# 4313_Breakout_V1_0.net
KiCad netlist of a schematic drawn in EAGLE
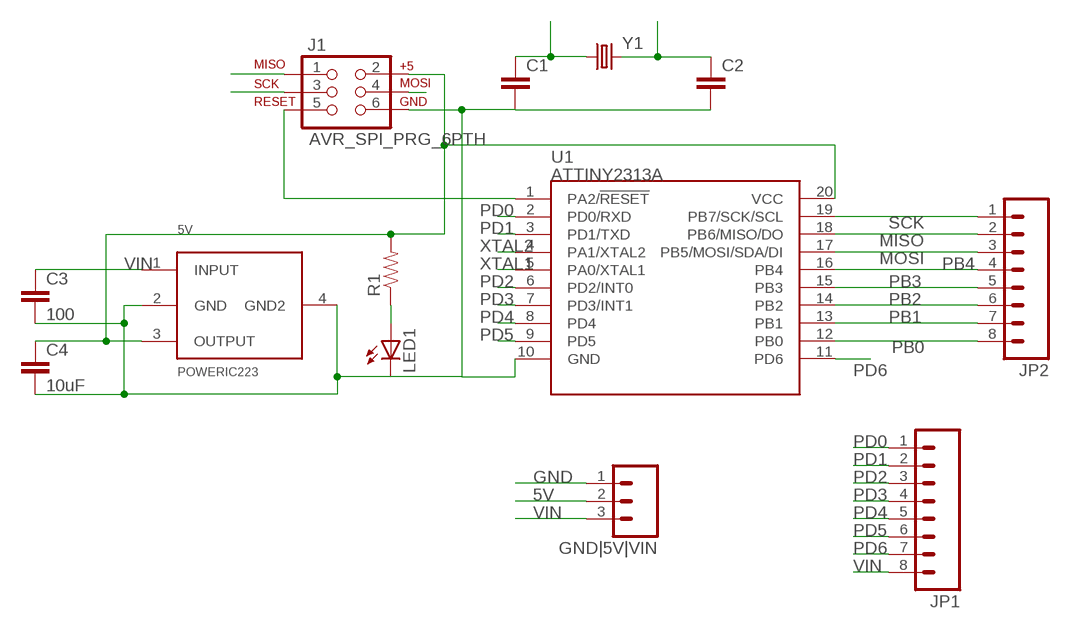
[diagram p0: schematic, sheet 1]

(export (version "E")
  (design (tool "Eeschema 10.0.6"))
  (components
    (comp (ref "5V")
      (value "POWERIC223")
      (footprint "eagle-import:SOT223")
      (libsource (lib "eagle-import") (part "POWERIC223"))
    )
    (comp (ref "C1")
      (value "CAP1206")
      (footprint "eagle-import:1206")
      (libsource (lib "eagle-import") (part "SparkFun-Passives_CAP1206"))
    )
    (comp (ref "C2")
      (value "CAP1206")
      (footprint "eagle-import:1206")
      (libsource (lib "eagle-import") (part "SparkFun-Passives_CAP1206"))
    )
    (comp (ref "C3")
      (value "100")
      (footprint "eagle-import:1210")
      (libsource (lib "eagle-import") (part "CAP1210"))
    )
    (comp (ref "C4")
      (value "10uF")
      (footprint "eagle-import:1210")
      (libsource (lib "eagle-import") (part "CAP1210"))
    )
    (comp (ref "GND|5V|VIN")
      (value "M03PTH")
      (footprint "eagle-import:1X03")
      (libsource (lib "eagle-import") (part "M03PTH"))
    )
    (comp (ref "J1")
      (value "AVR_SPI_PRG_6PTH")
      (footprint "eagle-import:2X3")
      (libsource (lib "eagle-import") (part "AVR_SPI_PRG_6PTH"))
    )
    (comp (ref "JP1")
      (value "M081X08")
      (footprint "eagle-import:1X08")
      (libsource (lib "eagle-import") (part "M081X08"))
    )
    (comp (ref "JP2")
      (value "M081X08")
      (footprint "eagle-import:1X08")
      (libsource (lib "eagle-import") (part "M081X08"))
    )
    (comp (ref "LED1")
      (value "LED1206")
      (footprint "eagle-import:LED-1206")
      (libsource (lib "eagle-import") (part "LED1206"))
    )
    (comp (ref "R1")
      (value "RESISTOR1206")
      (footprint "eagle-import:1206")
      (libsource (lib "eagle-import") (part "RESISTOR1206"))
    )
    (comp (ref "U1")
      (value "ATTINY2313A")
      (footprint "eagle-import:SOP20W")
      (libsource (lib "eagle-import") (part "ATTINY2313A"))
    )
    (comp (ref "Y1")
      (value "CRYSTALHC49US")
      (footprint "eagle-import:HC49US")
      (libsource (lib "eagle-import") (part "CRYSTALHC49US"))
    )
  )
  (nets
    (net (code "1") (name "/5V") (class "Default")
      (node (ref "5V") (pin "3") (pinfunction "OUTPUT_3") (pintype "bidirectional"))
      (node (ref "C4") (pin "1") (pinfunction "1_1") (pintype "passive"))
      (node (ref "GND|5V|VIN") (pin "2") (pinfunction "2_2") (pintype "passive"))
      (node (ref "J1") (pin "2") (pinfunction "2_2") (pintype "passive"))
      (node (ref "R1") (pin "2") (pinfunction "2_2") (pintype "passive"))
      (node (ref "U1") (pin "20") (pinfunction "VCC_20") (pintype "bidirectional"))
    )
    (net (code "2") (name "/GND") (class "Default")
      (node (ref "5V") (pin "2") (pinfunction "GND_2") (pintype "bidirectional"))
      (node (ref "5V") (pin "4") (pinfunction "GND2_4") (pintype "bidirectional"))
      (node (ref "C1") (pin "2") (pinfunction "2_2") (pintype "passive"))
      (node (ref "C2") (pin "2") (pinfunction "2_2") (pintype "passive"))
      (node (ref "C3") (pin "2") (pinfunction "2_2") (pintype "passive"))
      (node (ref "C4") (pin "2") (pinfunction "2_2") (pintype "passive"))
      (node (ref "GND|5V|VIN") (pin "1") (pinfunction "1_1") (pintype "passive"))
      (node (ref "J1") (pin "6") (pinfunction "6_6") (pintype "passive"))
      (node (ref "LED1") (pin "C") (pinfunction "C_C") (pintype "passive"))
      (node (ref "U1") (pin "10") (pinfunction "GND_10") (pintype "bidirectional"))
    )
    (net (code "3") (name "/MISO") (class "Default")
      (node (ref "J1") (pin "1") (pinfunction "1_1") (pintype "passive"))
      (node (ref "JP2") (pin "2") (pinfunction "2_2") (pintype "passive"))
      (node (ref "U1") (pin "18") (pinfunction "PB6/MISO/DO_18") (pintype "bidirectional"))
    )
    (net (code "4") (name "/MOSI") (class "Default")
      (node (ref "J1") (pin "4") (pinfunction "4_4") (pintype "passive"))
      (node (ref "JP2") (pin "3") (pinfunction "3_3") (pintype "passive"))
      (node (ref "U1") (pin "17") (pinfunction "PB5/MOSI/SDA/DI_17") (pintype "bidirectional"))
    )
    (net (code "5") (name "/PB0") (class "Default")
      (node (ref "JP2") (pin "8") (pinfunction "8_8") (pintype "passive"))
      (node (ref "U1") (pin "12") (pinfunction "PB0_12") (pintype "bidirectional"))
    )
    (net (code "6") (name "/PB1") (class "Default")
      (node (ref "JP2") (pin "7") (pinfunction "7_7") (pintype "passive"))
      (node (ref "U1") (pin "13") (pinfunction "PB1_13") (pintype "bidirectional"))
    )
    (net (code "7") (name "/PB2") (class "Default")
      (node (ref "JP2") (pin "6") (pinfunction "6_6") (pintype "passive"))
      (node (ref "U1") (pin "14") (pinfunction "PB2_14") (pintype "bidirectional"))
    )
    (net (code "8") (name "/PB3") (class "Default")
      (node (ref "JP2") (pin "5") (pinfunction "5_5") (pintype "passive"))
      (node (ref "U1") (pin "15") (pinfunction "PB3_15") (pintype "bidirectional"))
    )
    (net (code "9") (name "/PB4") (class "Default")
      (node (ref "JP2") (pin "4") (pinfunction "4_4") (pintype "passive"))
      (node (ref "U1") (pin "16") (pinfunction "PB4_16") (pintype "bidirectional"))
    )
    (net (code "10") (name "/PD0") (class "Default")
      (node (ref "JP1") (pin "1") (pinfunction "1_1") (pintype "passive"))
      (node (ref "U1") (pin "2") (pinfunction "PD0/RXD_2") (pintype "bidirectional"))
    )
    (net (code "11") (name "/PD1") (class "Default")
      (node (ref "JP1") (pin "2") (pinfunction "2_2") (pintype "passive"))
      (node (ref "U1") (pin "3") (pinfunction "PD1/TXD_3") (pintype "bidirectional"))
    )
    (net (code "12") (name "/PD2") (class "Default")
      (node (ref "JP1") (pin "3") (pinfunction "3_3") (pintype "passive"))
      (node (ref "U1") (pin "6") (pinfunction "PD2/INT0_6") (pintype "bidirectional"))
    )
    (net (code "13") (name "/PD3") (class "Default")
      (node (ref "JP1") (pin "4") (pinfunction "4_4") (pintype "passive"))
      (node (ref "U1") (pin "7") (pinfunction "PD3/INT1_7") (pintype "bidirectional"))
    )
    (net (code "14") (name "/PD4") (class "Default")
      (node (ref "JP1") (pin "5") (pinfunction "5_5") (pintype "passive"))
      (node (ref "U1") (pin "8") (pinfunction "PD4_8") (pintype "bidirectional"))
    )
    (net (code "15") (name "/PD5") (class "Default")
      (node (ref "JP1") (pin "6") (pinfunction "6_6") (pintype "passive"))
      (node (ref "U1") (pin "9") (pinfunction "PD5_9") (pintype "bidirectional"))
    )
    (net (code "16") (name "/PD6") (class "Default")
      (node (ref "JP1") (pin "7") (pinfunction "7_7") (pintype "passive"))
      (node (ref "U1") (pin "11") (pinfunction "PD6_11") (pintype "bidirectional"))
    )
    (net (code "17") (name "/SCK") (class "Default")
      (node (ref "J1") (pin "3") (pinfunction "3_3") (pintype "passive"))
      (node (ref "JP2") (pin "1") (pinfunction "1_1") (pintype "passive"))
      (node (ref "U1") (pin "19") (pinfunction "PB7/SCK/SCL_19") (pintype "bidirectional"))
    )
    (net (code "18") (name "/VIN") (class "Default")
      (node (ref "5V") (pin "1") (pinfunction "INPUT_1") (pintype "bidirectional"))
      (node (ref "C3") (pin "1") (pinfunction "1_1") (pintype "passive"))
      (node (ref "GND|5V|VIN") (pin "3") (pinfunction "3_3") (pintype "passive"))
      (node (ref "JP1") (pin "8") (pinfunction "8_8") (pintype "passive"))
    )
    (net (code "19") (name "/XTAL1") (class "Default")
      (node (ref "C1") (pin "1") (pinfunction "1_1") (pintype "passive"))
      (node (ref "U1") (pin "5") (pinfunction "PA0/XTAL1_5") (pintype "bidirectional"))
      (node (ref "Y1") (pin "1") (pinfunction "1_1") (pintype "passive"))
    )
    (net (code "20") (name "/XTAL2") (class "Default")
      (node (ref "C2") (pin "1") (pinfunction "1_1") (pintype "passive"))
      (node (ref "U1") (pin "4") (pinfunction "PA1/XTAL2_4") (pintype "bidirectional"))
      (node (ref "Y1") (pin "2") (pinfunction "2_2") (pintype "passive"))
    )
    (net (code "21") (name "Net-(LED1-PadA)") (class "Default")
      (node (ref "LED1") (pin "A") (pinfunction "A_A") (pintype "passive"))
      (node (ref "R1") (pin "1") (pinfunction "1_1") (pintype "passive"))
    )
    (net (code "22") (name "Net-(U1-PA2{slash}~{RESET})") (class "Default")
      (node (ref "J1") (pin "5") (pinfunction "5_5") (pintype "passive"))
      (node (ref "U1") (pin "1") (pinfunction "PA2/~{RESET}_1") (pintype "bidirectional"))
    )
  )
)
